# LHC_audio.net
KiCad netlist of a schematic drawn in Altium Designer
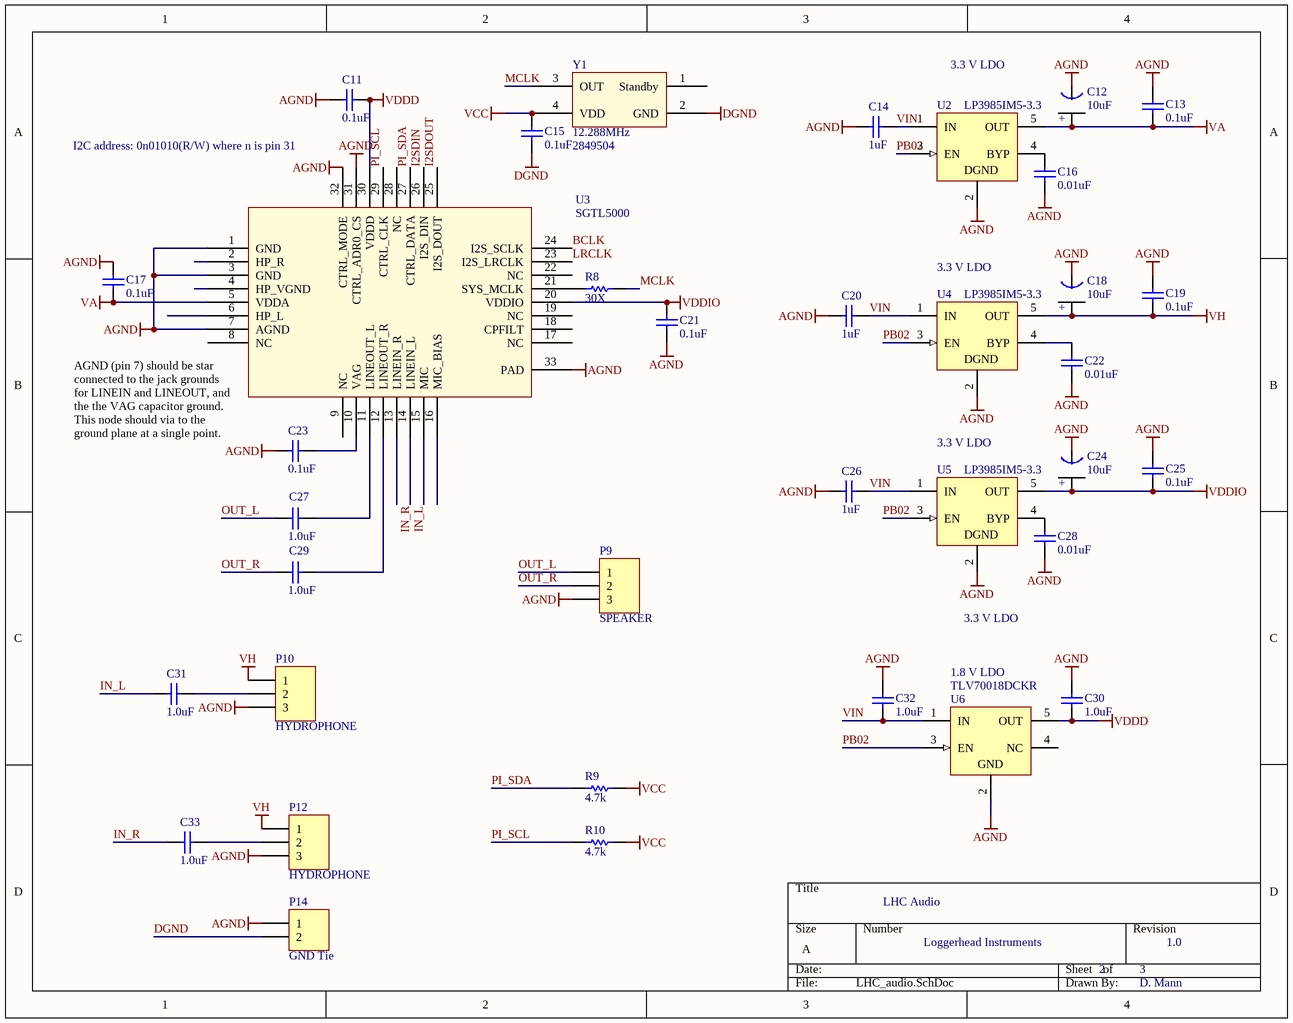
[diagram p0: LHC_audio.SchDoc]

(export (version "E")
  (design (tool "Eeschema 10.0.6"))
  (components
    (comp (ref "C11")
      (value "0.1uF")
      (footprint "0402")
      (description "Ceramic Chip Capacitor - Standard")
      (fields (field (name "PUBLISHER") "Altium Limited"))
      (libsource (lib "KEMET Chip Capacitor") (part "C0402"))
    )
    (comp (ref "C12") (value "10uF") (footprint "Tant0805") (libsource (lib "Loggerhead") (part "Tant0805")))
    (comp (ref "C13")
      (value "0.1uF")
      (footprint "0402")
      (description "Ceramic Chip Capacitor - Standard")
      (fields (field (name "PUBLISHER") "Altium Limited"))
      (libsource (lib "KEMET Chip Capacitor") (part "C0402"))
    )
    (comp (ref "C14")
      (value "1uF")
      (footprint "0402")
      (description "Ceramic Chip Capacitor - Standard")
      (fields (field (name "PUBLISHER") "Altium Limited"))
      (libsource (lib "KEMET Chip Capacitor") (part "C0402"))
    )
    (comp (ref "C15")
      (value "0.1uF")
      (footprint "0402")
      (description "Ceramic Chip Capacitor - Standard")
      (fields (field (name "PUBLISHER") "Altium Limited"))
      (libsource (lib "KEMET Chip Capacitor") (part "C0402"))
    )
    (comp (ref "C16")
      (value "0.01uF")
      (footprint "0402")
      (description "Ceramic Chip Capacitor - Standard")
      (fields (field (name "PUBLISHER") "Altium Limited"))
      (libsource (lib "KEMET Chip Capacitor") (part "C0402"))
    )
    (comp (ref "C17")
      (value "0.1uF")
      (footprint "0402")
      (description "Ceramic Chip Capacitor - Standard")
      (fields (field (name "PUBLISHER") "Altium Limited"))
      (libsource (lib "KEMET Chip Capacitor") (part "C0402"))
    )
    (comp (ref "C18") (value "10uF") (footprint "Tant0805") (libsource (lib "Loggerhead") (part "Tant0805")))
    (comp (ref "C19")
      (value "0.1uF")
      (footprint "0402")
      (description "Ceramic Chip Capacitor - Standard")
      (fields (field (name "PUBLISHER") "Altium Limited"))
      (libsource (lib "KEMET Chip Capacitor") (part "C0402"))
    )
    (comp (ref "C20")
      (value "1uF")
      (footprint "0402")
      (description "Ceramic Chip Capacitor - Standard")
      (fields (field (name "PUBLISHER") "Altium Limited"))
      (libsource (lib "KEMET Chip Capacitor") (part "C0402"))
    )
    (comp (ref "C21")
      (value "0.1uF")
      (footprint "0402")
      (description "Ceramic Chip Capacitor - Standard")
      (fields (field (name "PUBLISHER") "Altium Limited"))
      (libsource (lib "KEMET Chip Capacitor") (part "C0402"))
    )
    (comp (ref "C22")
      (value "0.01uF")
      (footprint "0402")
      (description "Ceramic Chip Capacitor - Standard")
      (fields (field (name "PUBLISHER") "Altium Limited"))
      (libsource (lib "KEMET Chip Capacitor") (part "C0402"))
    )
    (comp (ref "C23")
      (value "0.1uF")
      (footprint "0402")
      (description "Ceramic Chip Capacitor - Standard")
      (fields (field (name "PUBLISHER") "Altium Limited"))
      (libsource (lib "KEMET Chip Capacitor") (part "C0402"))
    )
    (comp (ref "C24") (value "10uF") (footprint "Tant0805") (libsource (lib "Loggerhead") (part "Tant0805")))
    (comp (ref "C25")
      (value "0.1uF")
      (footprint "0402")
      (description "Ceramic Chip Capacitor - Standard")
      (fields (field (name "PUBLISHER") "Altium Limited"))
      (libsource (lib "KEMET Chip Capacitor") (part "C0402"))
    )
    (comp (ref "C26")
      (value "1uF")
      (footprint "0402")
      (description "Ceramic Chip Capacitor - Standard")
      (fields (field (name "PUBLISHER") "Altium Limited"))
      (libsource (lib "KEMET Chip Capacitor") (part "C0402"))
    )
    (comp (ref "C27")
      (value "1.0uF")
      (footprint "0402")
      (description "Ceramic Chip Capacitor - Standard")
      (fields (field (name "PUBLISHER") "Altium Limited"))
      (libsource (lib "KEMET Chip Capacitor") (part "C0402"))
    )
    (comp (ref "C28")
      (value "0.01uF")
      (footprint "0402")
      (description "Ceramic Chip Capacitor - Standard")
      (fields (field (name "PUBLISHER") "Altium Limited"))
      (libsource (lib "KEMET Chip Capacitor") (part "C0402"))
    )
    (comp (ref "C29")
      (value "1.0uF")
      (footprint "0402")
      (description "Ceramic Chip Capacitor - Standard")
      (fields (field (name "PUBLISHER") "Altium Limited"))
      (libsource (lib "KEMET Chip Capacitor") (part "C0402"))
    )
    (comp (ref "C30")
      (value "1.0uF")
      (footprint "0402")
      (description "Ceramic Chip Capacitor - Standard")
      (fields (field (name "PUBLISHER") "Altium Limited"))
      (libsource (lib "KEMET Chip Capacitor") (part "C0402"))
    )
    (comp (ref "C31")
      (value "1.0uF")
      (footprint "0402")
      (description "Ceramic Chip Capacitor - Standard")
      (fields (field (name "PUBLISHER") "Altium Limited"))
      (libsource (lib "KEMET Chip Capacitor") (part "C0402"))
    )
    (comp (ref "C32")
      (value "1.0uF")
      (footprint "0402")
      (description "Ceramic Chip Capacitor - Standard")
      (fields (field (name "PUBLISHER") "Altium Limited"))
      (libsource (lib "KEMET Chip Capacitor") (part "C0402"))
    )
    (comp (ref "C33")
      (value "1.0uF")
      (footprint "0402")
      (description "Ceramic Chip Capacitor - Standard")
      (fields (field (name "PUBLISHER") "Altium Limited"))
      (libsource (lib "KEMET Chip Capacitor") (part "C0402"))
    )
    (comp (ref "P9")
      (value "SPEAKER")
      (footprint "HDR1X3")
      (description "Header, 3-Pin")
      (fields (field (name "PUBLISHER") "Altium Limited"))
      (libsource (lib "Miscellaneous Connectors") (part "Header 3"))
    )
    (comp (ref "P10")
      (value "HYDROPHONE")
      (footprint "HDR1X3")
      (description "Header, 3-Pin")
      (fields (field (name "PUBLISHER") "Altium Limited"))
      (libsource (lib "Miscellaneous Connectors") (part "Header 3"))
    )
    (comp (ref "P12")
      (value "HYDROPHONE")
      (footprint "HDR1X3")
      (description "Header, 3-Pin")
      (fields (field (name "PUBLISHER") "Altium Limited"))
      (libsource (lib "Miscellaneous Connectors") (part "Header 3"))
    )
    (comp (ref "P14")
      (value "GND Tie")
      (footprint "HDR1X2")
      (description "Header, 2-Pin")
      (fields (field (name "PUBLISHER") "Altium Limited"))
      (libsource (lib "Miscellaneous Connectors") (part "Header 2"))
    )
    (comp (ref "R8")
      (value "30X")
      (footprint "3-0603")
      (fields (field (name "PUBLISHER") "Altium Limited"))
      (libsource (lib "Panasonic Resistor") (part "ERJ3RK"))
    )
    (comp (ref "R9")
      (value "4.7k")
      (footprint "3-0603")
      (fields (field (name "PUBLISHER") "Altium Limited"))
      (libsource (lib "Panasonic Resistor") (part "ERJ3RK"))
    )
    (comp (ref "R10")
      (value "4.7k")
      (footprint "3-0603")
      (fields (field (name "PUBLISHER") "Altium Limited"))
      (libsource (lib "Panasonic Resistor") (part "ERJ3RK"))
    )
    (comp (ref "U2")
      (value "LP3985IM5-3.3")
      (footprint "MF05A_N")
      (description "Micropower, 150mA Low-Noise Ultra Low-Dropout CMOS Voltage Regulator")
      (fields
        (field (name "MANUFACTURER") "National Semiconductor")
        (field (name "DIGIKEYPARTNUMBER") "LP3985IM5-3.3CT-ND")
        (field (name "PUBLISHER") "Altium Limited")
      )
      (libsource (lib "NSC LDO") (part "LP3985IM5-3.3"))
    )
    (comp (ref "U3") (value "SGTL5000") (footprint "QFN32") (libsource (lib "Loggerhead") (part "SGTL5000")))
    (comp (ref "U4")
      (value "LP3985IM5-3.3")
      (footprint "MF05A_N")
      (description "Micropower, 150mA Low-Noise Ultra Low-Dropout CMOS Voltage Regulator")
      (fields
        (field (name "MANUFACTURER") "National Semiconductor")
        (field (name "DIGIKEYPARTNUMBER") "LP3985IM5-3.3CT-ND")
        (field (name "PUBLISHER") "Altium Limited")
      )
      (libsource (lib "NSC LDO") (part "LP3985IM5-3.3"))
    )
    (comp (ref "U5")
      (value "LP3985IM5-3.3")
      (footprint "MF05A_N")
      (description "Micropower, 150mA Low-Noise Ultra Low-Dropout CMOS Voltage Regulator")
      (fields
        (field (name "MANUFACTURER") "National Semiconductor")
        (field (name "DIGIKEYPARTNUMBER") "LP3985IM5-3.3CT-ND")
        (field (name "PUBLISHER") "Altium Limited")
      )
      (libsource (lib "NSC LDO") (part "LP3985IM5-3.3"))
    )
    (comp (ref "U6")
      (value "TLV70018DCKR")
      (footprint "TI-DCK5_V")
      (fields (field (name "MANUFACTURER") "Texas Instruments"))
      (libsource (lib "TI Power Management Linear Regulator Single Channel LDO (0-350mA)") (part "TLV70018DCKR"))
    )
    (comp (ref "Y1")
      (value "12.288MHz")
      (footprint "Oscillator_5x3.2")
      (fields (field (name "SUPPLIER PART NUMBER 1") "2849504"))
      (libsource (lib "Loggerhead") (part "Oscillator_5x3.2"))
    )
  )
  (nets
    (net (code "1") (name "/BCLK") (class "Default")
      (node (ref "U3") (pin "24") (pinfunction "I2S_SCLK_24") (pintype "passive"))
    )
    (net (code "2") (name "/I2SDIN") (class "Default")
      (node (ref "U3") (pin "26") (pinfunction "I2S_DIN_26") (pintype "passive"))
    )
    (net (code "3") (name "/I2SDOUT") (class "Default")
      (node (ref "U3") (pin "25") (pinfunction "I2S_DOUT_25") (pintype "passive"))
    )
    (net (code "4") (name "/IN_L") (class "Default")
      (node (ref "C31") (pin "2") (pinfunction "2_2") (pintype "passive"))
      (node (ref "U3") (pin "14") (pinfunction "LINEIN_L_14") (pintype "passive"))
    )
    (net (code "5") (name "/IN_R") (class "Default")
      (node (ref "C33") (pin "2") (pinfunction "2_2") (pintype "passive"))
      (node (ref "U3") (pin "13") (pinfunction "LINEIN_R_13") (pintype "passive"))
    )
    (net (code "6") (name "/LRCLK") (class "Default")
      (node (ref "U3") (pin "23") (pinfunction "I2S_LRCLK_23") (pintype "passive"))
    )
    (net (code "7") (name "/MCLK") (class "Default")
      (node (ref "R8") (pin "2") (pinfunction "2_2") (pintype "passive"))
      (node (ref "Y1") (pin "3") (pinfunction "OUT_3") (pintype "passive"))
    )
    (net (code "8") (name "/OUT_L") (class "Default")
      (node (ref "C27") (pin "1") (pinfunction "1_1") (pintype "passive"))
      (node (ref "P9") (pin "1") (pinfunction "1_1") (pintype "passive"))
    )
    (net (code "9") (name "/OUT_R") (class "Default")
      (node (ref "C29") (pin "1") (pinfunction "1_1") (pintype "passive"))
      (node (ref "P9") (pin "2") (pinfunction "2_2") (pintype "passive"))
    )
    (net (code "10") (name "/PB02") (class "Default")
      (node (ref "U2") (pin "3") (pinfunction "EN_3") (pintype "input"))
      (node (ref "U4") (pin "3") (pinfunction "EN_3") (pintype "input"))
      (node (ref "U5") (pin "3") (pinfunction "EN_3") (pintype "input"))
      (node (ref "U6") (pin "3") (pinfunction "EN_3") (pintype "input"))
    )
    (net (code "11") (name "/PI_SCL") (class "Default")
      (node (ref "R10") (pin "1") (pinfunction "1_1") (pintype "passive"))
      (node (ref "U3") (pin "29") (pinfunction "CTRL_CLK_29") (pintype "passive"))
    )
    (net (code "12") (name "/PI_SDA") (class "Default")
      (node (ref "R9") (pin "1") (pinfunction "1_1") (pintype "passive"))
      (node (ref "U3") (pin "27") (pinfunction "CTRL_DATA_27") (pintype "passive"))
    )
    (net (code "13") (name "/VIN") (class "Default")
      (node (ref "C14") (pin "1") (pinfunction "1_1") (pintype "passive"))
      (node (ref "C20") (pin "1") (pinfunction "1_1") (pintype "passive"))
      (node (ref "C26") (pin "1") (pinfunction "1_1") (pintype "passive"))
      (node (ref "C32") (pin "1") (pinfunction "1_1") (pintype "passive"))
      (node (ref "U2") (pin "1") (pinfunction "IN_1") (pintype "power_in"))
      (node (ref "U4") (pin "1") (pinfunction "IN_1") (pintype "power_in"))
      (node (ref "U5") (pin "1") (pinfunction "IN_1") (pintype "power_in"))
      (node (ref "U6") (pin "1") (pinfunction "IN_1") (pintype "power_in"))
    )
    (net (code "14") (name "AGND") (class "Default")
      (node (ref "C11") (pin "2") (pinfunction "2_2") (pintype "passive"))
      (node (ref "C12") (pin "1") (pinfunction "GND_1") (pintype "passive"))
      (node (ref "C13") (pin "2") (pinfunction "2_2") (pintype "passive"))
      (node (ref "C14") (pin "2") (pinfunction "2_2") (pintype "passive"))
      (node (ref "C16") (pin "2") (pinfunction "2_2") (pintype "passive"))
      (node (ref "C17") (pin "2") (pinfunction "2_2") (pintype "passive"))
      (node (ref "C18") (pin "1") (pinfunction "GND_1") (pintype "passive"))
      (node (ref "C19") (pin "2") (pinfunction "2_2") (pintype "passive"))
      (node (ref "C20") (pin "2") (pinfunction "2_2") (pintype "passive"))
      (node (ref "C21") (pin "2") (pinfunction "2_2") (pintype "passive"))
      (node (ref "C22") (pin "2") (pinfunction "2_2") (pintype "passive"))
      (node (ref "C23") (pin "2") (pinfunction "2_2") (pintype "passive"))
      (node (ref "C24") (pin "1") (pinfunction "GND_1") (pintype "passive"))
      (node (ref "C25") (pin "2") (pinfunction "2_2") (pintype "passive"))
      (node (ref "C26") (pin "2") (pinfunction "2_2") (pintype "passive"))
      (node (ref "C28") (pin "2") (pinfunction "2_2") (pintype "passive"))
      (node (ref "C30") (pin "2") (pinfunction "2_2") (pintype "passive"))
      (node (ref "C32") (pin "2") (pinfunction "2_2") (pintype "passive"))
      (node (ref "P10") (pin "3") (pinfunction "3_3") (pintype "passive"))
      (node (ref "P12") (pin "3") (pinfunction "3_3") (pintype "passive"))
      (node (ref "P14") (pin "1") (pinfunction "1_1") (pintype "passive"))
      (node (ref "P9") (pin "3") (pinfunction "3_3") (pintype "passive"))
      (node (ref "U2") (pin "2") (pinfunction "GND_2") (pintype "power_in"))
      (node (ref "U3") (pin "1") (pinfunction "GND_1") (pintype "passive"))
      (node (ref "U3") (pin "3") (pinfunction "GND_3") (pintype "passive"))
      (node (ref "U3") (pin "31") (pinfunction "CTRL_ADR0_CS_31") (pintype "passive"))
      (node (ref "U3") (pin "32") (pinfunction "CTRL_MODE_32") (pintype "passive"))
      (node (ref "U3") (pin "33") (pinfunction "PAD_33") (pintype "passive"))
      (node (ref "U3") (pin "7") (pinfunction "AGND_7") (pintype "passive"))
      (node (ref "U4") (pin "2") (pinfunction "GND_2") (pintype "power_in"))
      (node (ref "U5") (pin "2") (pinfunction "GND_2") (pintype "power_in"))
      (node (ref "U6") (pin "2") (pinfunction "GND_2") (pintype "power_in"))
    )
    (net (code "15") (name "DGND") (class "Default")
      (node (ref "C15") (pin "2") (pinfunction "2_2") (pintype "passive"))
      (node (ref "P14") (pin "2") (pinfunction "2_2") (pintype "passive"))
      (node (ref "Y1") (pin "2") (pinfunction "GND_2") (pintype "passive"))
    )
    (net (code "16") (name "Net-(C31-Pad1)") (class "Default")
      (node (ref "C31") (pin "1") (pinfunction "1_1") (pintype "passive"))
      (node (ref "P10") (pin "2") (pinfunction "2_2") (pintype "passive"))
    )
    (net (code "17") (name "Net-(C33-Pad1)") (class "Default")
      (node (ref "C33") (pin "1") (pinfunction "1_1") (pintype "passive"))
      (node (ref "P12") (pin "2") (pinfunction "2_2") (pintype "passive"))
    )
    (net (code "18") (name "Net-(U2-BYP)") (class "Default")
      (node (ref "C16") (pin "1") (pinfunction "1_1") (pintype "passive"))
      (node (ref "U2") (pin "4") (pinfunction "BYP_4") (pintype "passive"))
    )
    (net (code "19") (name "Net-(U3-LINEOUT_L)") (class "Default")
      (node (ref "C27") (pin "2") (pinfunction "2_2") (pintype "passive"))
      (node (ref "U3") (pin "11") (pinfunction "LINEOUT_L_11") (pintype "passive"))
    )
    (net (code "20") (name "Net-(U3-LINEOUT_R)") (class "Default")
      (node (ref "C29") (pin "2") (pinfunction "2_2") (pintype "passive"))
      (node (ref "U3") (pin "12") (pinfunction "LINEOUT_R_12") (pintype "passive"))
    )
    (net (code "21") (name "Net-(U3-SYS_MCLK)") (class "Default")
      (node (ref "R8") (pin "1") (pinfunction "1_1") (pintype "passive"))
      (node (ref "U3") (pin "21") (pinfunction "SYS_MCLK_21") (pintype "passive"))
    )
    (net (code "22") (name "Net-(U3-VAG)") (class "Default")
      (node (ref "C23") (pin "1") (pinfunction "1_1") (pintype "passive"))
      (node (ref "U3") (pin "10") (pinfunction "VAG_10") (pintype "passive"))
    )
    (net (code "23") (name "Net-(U4-BYP)") (class "Default")
      (node (ref "C22") (pin "1") (pinfunction "1_1") (pintype "passive"))
      (node (ref "U4") (pin "4") (pinfunction "BYP_4") (pintype "passive"))
    )
    (net (code "24") (name "Net-(U5-BYP)") (class "Default")
      (node (ref "C28") (pin "1") (pinfunction "1_1") (pintype "passive"))
      (node (ref "U5") (pin "4") (pinfunction "BYP_4") (pintype "passive"))
    )
    (net (code "25") (name "VA") (class "Default")
      (node (ref "C12") (pin "2") (pinfunction "+_2") (pintype "passive"))
      (node (ref "C13") (pin "1") (pinfunction "1_1") (pintype "passive"))
      (node (ref "C17") (pin "1") (pinfunction "1_1") (pintype "passive"))
      (node (ref "U2") (pin "5") (pinfunction "OUT_5") (pintype "power_in"))
      (node (ref "U3") (pin "5") (pinfunction "VDDA_5") (pintype "passive"))
    )
    (net (code "26") (name "VCC") (class "Default")
      (node (ref "C15") (pin "1") (pinfunction "1_1") (pintype "passive"))
      (node (ref "R10") (pin "2") (pinfunction "2_2") (pintype "passive"))
      (node (ref "R9") (pin "2") (pinfunction "2_2") (pintype "passive"))
      (node (ref "Y1") (pin "4") (pinfunction "VDD_4") (pintype "passive"))
    )
    (net (code "27") (name "VDDD") (class "Default")
      (node (ref "C11") (pin "1") (pinfunction "1_1") (pintype "passive"))
      (node (ref "C30") (pin "1") (pinfunction "1_1") (pintype "passive"))
      (node (ref "U3") (pin "30") (pinfunction "VDDD_30") (pintype "passive"))
      (node (ref "U6") (pin "5") (pinfunction "OUT_5") (pintype "power_in"))
    )
    (net (code "28") (name "VDDIO") (class "Default")
      (node (ref "C21") (pin "1") (pinfunction "1_1") (pintype "passive"))
      (node (ref "C24") (pin "2") (pinfunction "+_2") (pintype "passive"))
      (node (ref "C25") (pin "1") (pinfunction "1_1") (pintype "passive"))
      (node (ref "U3") (pin "20") (pinfunction "VDDIO_20") (pintype "passive"))
      (node (ref "U5") (pin "5") (pinfunction "OUT_5") (pintype "power_in"))
    )
    (net (code "29") (name "VH") (class "Default")
      (node (ref "C18") (pin "2") (pinfunction "+_2") (pintype "passive"))
      (node (ref "C19") (pin "1") (pinfunction "1_1") (pintype "passive"))
      (node (ref "P10") (pin "1") (pinfunction "1_1") (pintype "passive"))
      (node (ref "P12") (pin "1") (pinfunction "1_1") (pintype "passive"))
      (node (ref "U4") (pin "5") (pinfunction "OUT_5") (pintype "power_in"))
    )
    (net (code "30") (name "unconnected-(U3-CPFILT-Pad18)") (class "Default")
      (node (ref "U3") (pin "18") (pinfunction "CPFILT_18") (pintype "passive"))
    )
    (net (code "31") (name "unconnected-(U3-HP_L-Pad6)") (class "Default")
      (node (ref "U3") (pin "6") (pinfunction "HP_L_6") (pintype "passive"))
    )
    (net (code "32") (name "unconnected-(U3-HP_R-Pad2)") (class "Default")
      (node (ref "U3") (pin "2") (pinfunction "HP_R_2") (pintype "passive"))
    )
    (net (code "33") (name "unconnected-(U3-HP_VGND-Pad4)") (class "Default")
      (node (ref "U3") (pin "4") (pinfunction "HP_VGND_4") (pintype "passive"))
    )
    (net (code "34") (name "unconnected-(U3-MIC-Pad15)") (class "Default")
      (node (ref "U3") (pin "15") (pinfunction "MIC_15") (pintype "passive"))
    )
    (net (code "35") (name "unconnected-(U3-MIC_BIAS-Pad16)") (class "Default")
      (node (ref "U3") (pin "16") (pinfunction "MIC_BIAS_16") (pintype "passive"))
    )
    (net (code "36") (name "unconnected-(U3-NC-Pad8)") (class "Default")
      (node (ref "U3") (pin "8") (pinfunction "NC_8") (pintype "passive"))
    )
    (net (code "37") (name "unconnected-(U3-NC-Pad9)") (class "Default")
      (node (ref "U3") (pin "9") (pinfunction "NC_9") (pintype "passive"))
    )
    (net (code "38") (name "unconnected-(U3-NC-Pad17)") (class "Default")
      (node (ref "U3") (pin "17") (pinfunction "NC_17") (pintype "passive"))
    )
    (net (code "39") (name "unconnected-(U3-NC-Pad19)") (class "Default")
      (node (ref "U3") (pin "19") (pinfunction "NC_19") (pintype "passive"))
    )
    (net (code "40") (name "unconnected-(U3-NC-Pad22)") (class "Default")
      (node (ref "U3") (pin "22") (pinfunction "NC_22") (pintype "passive"))
    )
    (net (code "41") (name "unconnected-(U3-NC-Pad28)") (class "Default")
      (node (ref "U3") (pin "28") (pinfunction "NC_28") (pintype "passive"))
    )
    (net (code "42") (name "unconnected-(U6-NC-Pad4)") (class "Default")
      (node (ref "U6") (pin "4") (pinfunction "NC_4") (pintype "passive"))
    )
    (net (code "43") (name "unconnected-(Y1-Standby-Pad1)") (class "Default")
      (node (ref "Y1") (pin "1") (pinfunction "Standby_1") (pintype "passive"))
    )
  )
)
